# Module-Extension_V101.net
KiCad netlist of a schematic drawn in EAGLE
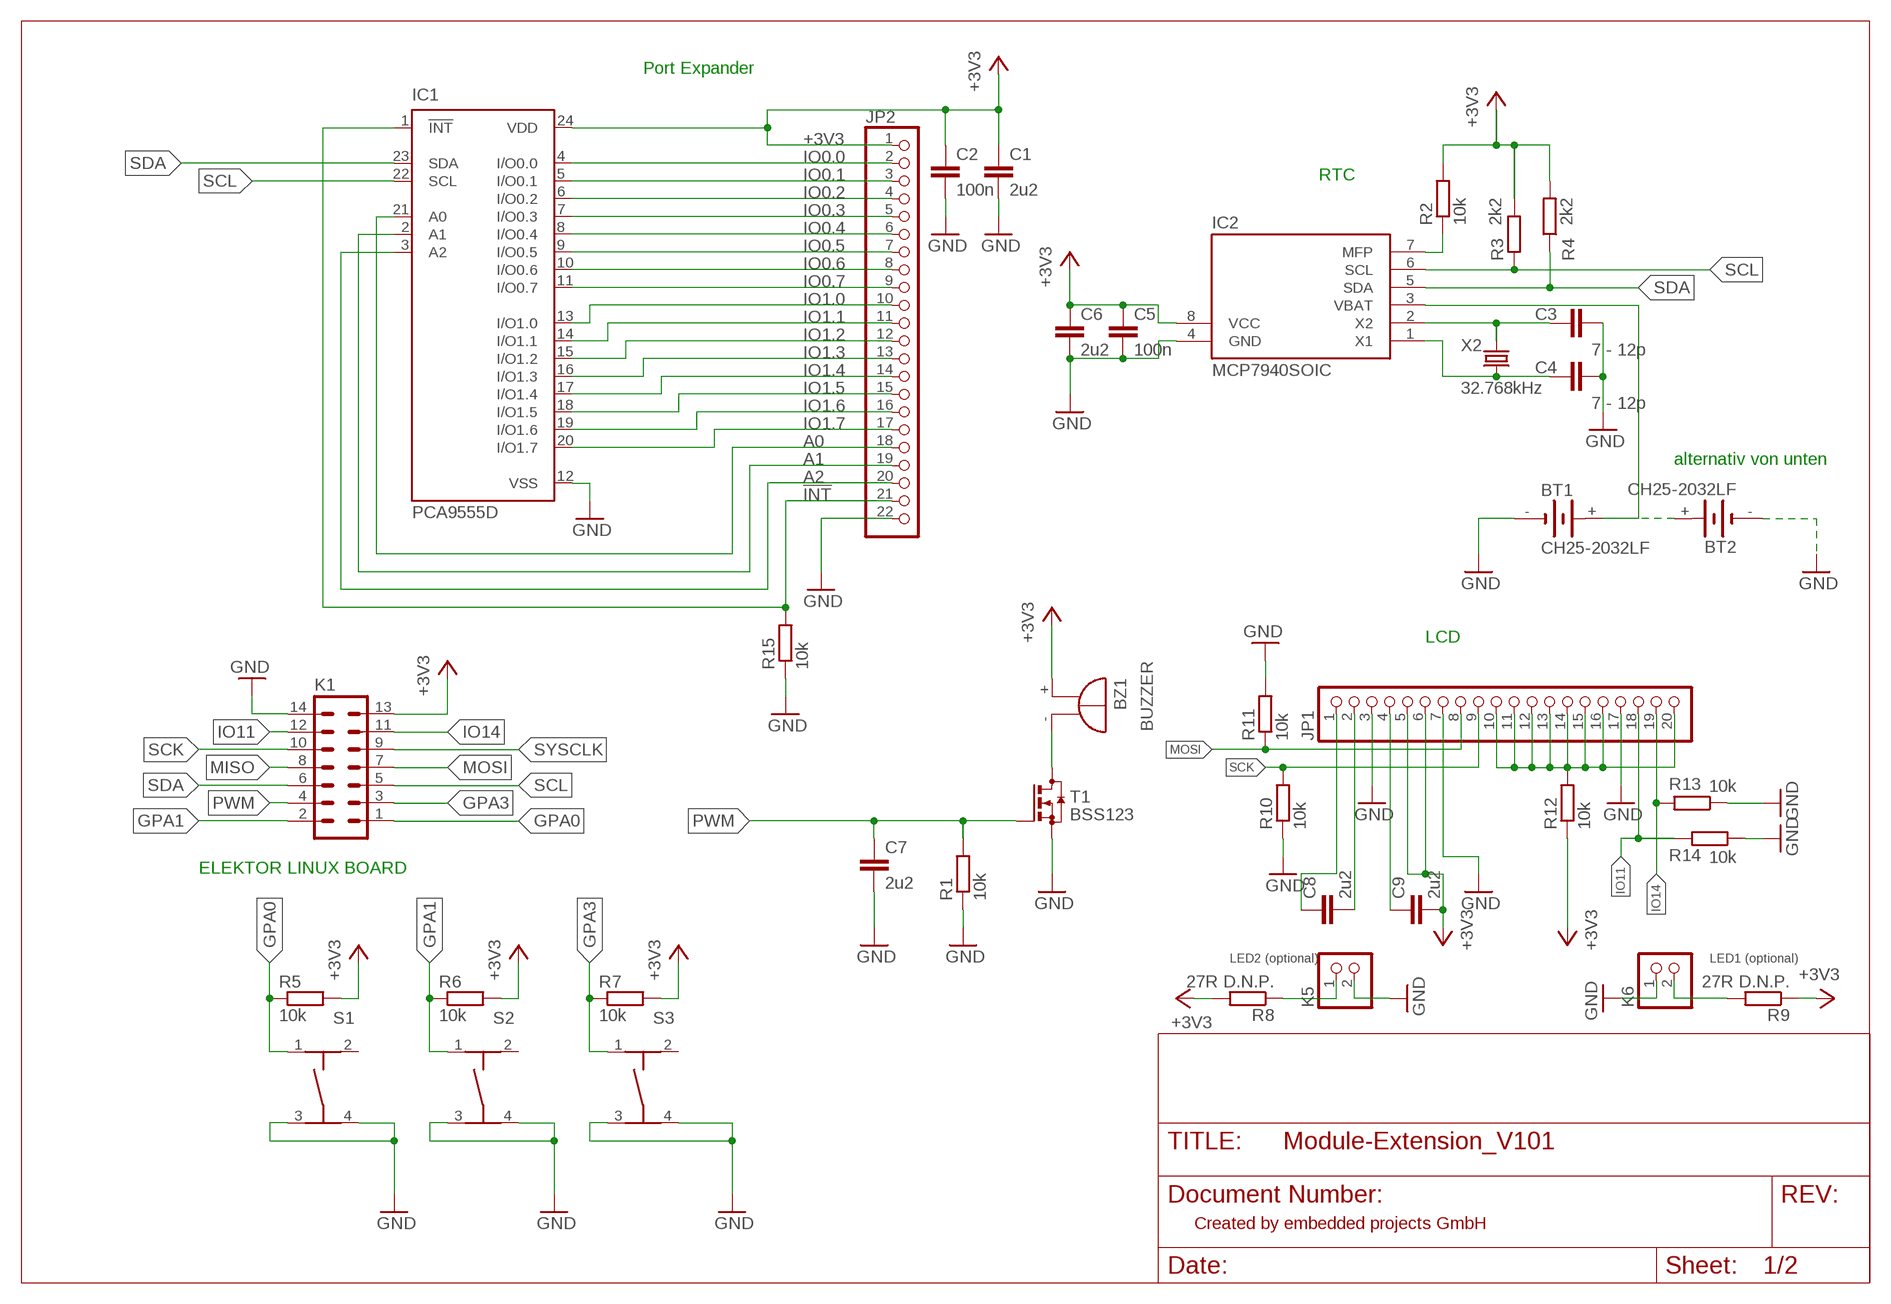
[diagram p0: schematic, sheet 1]
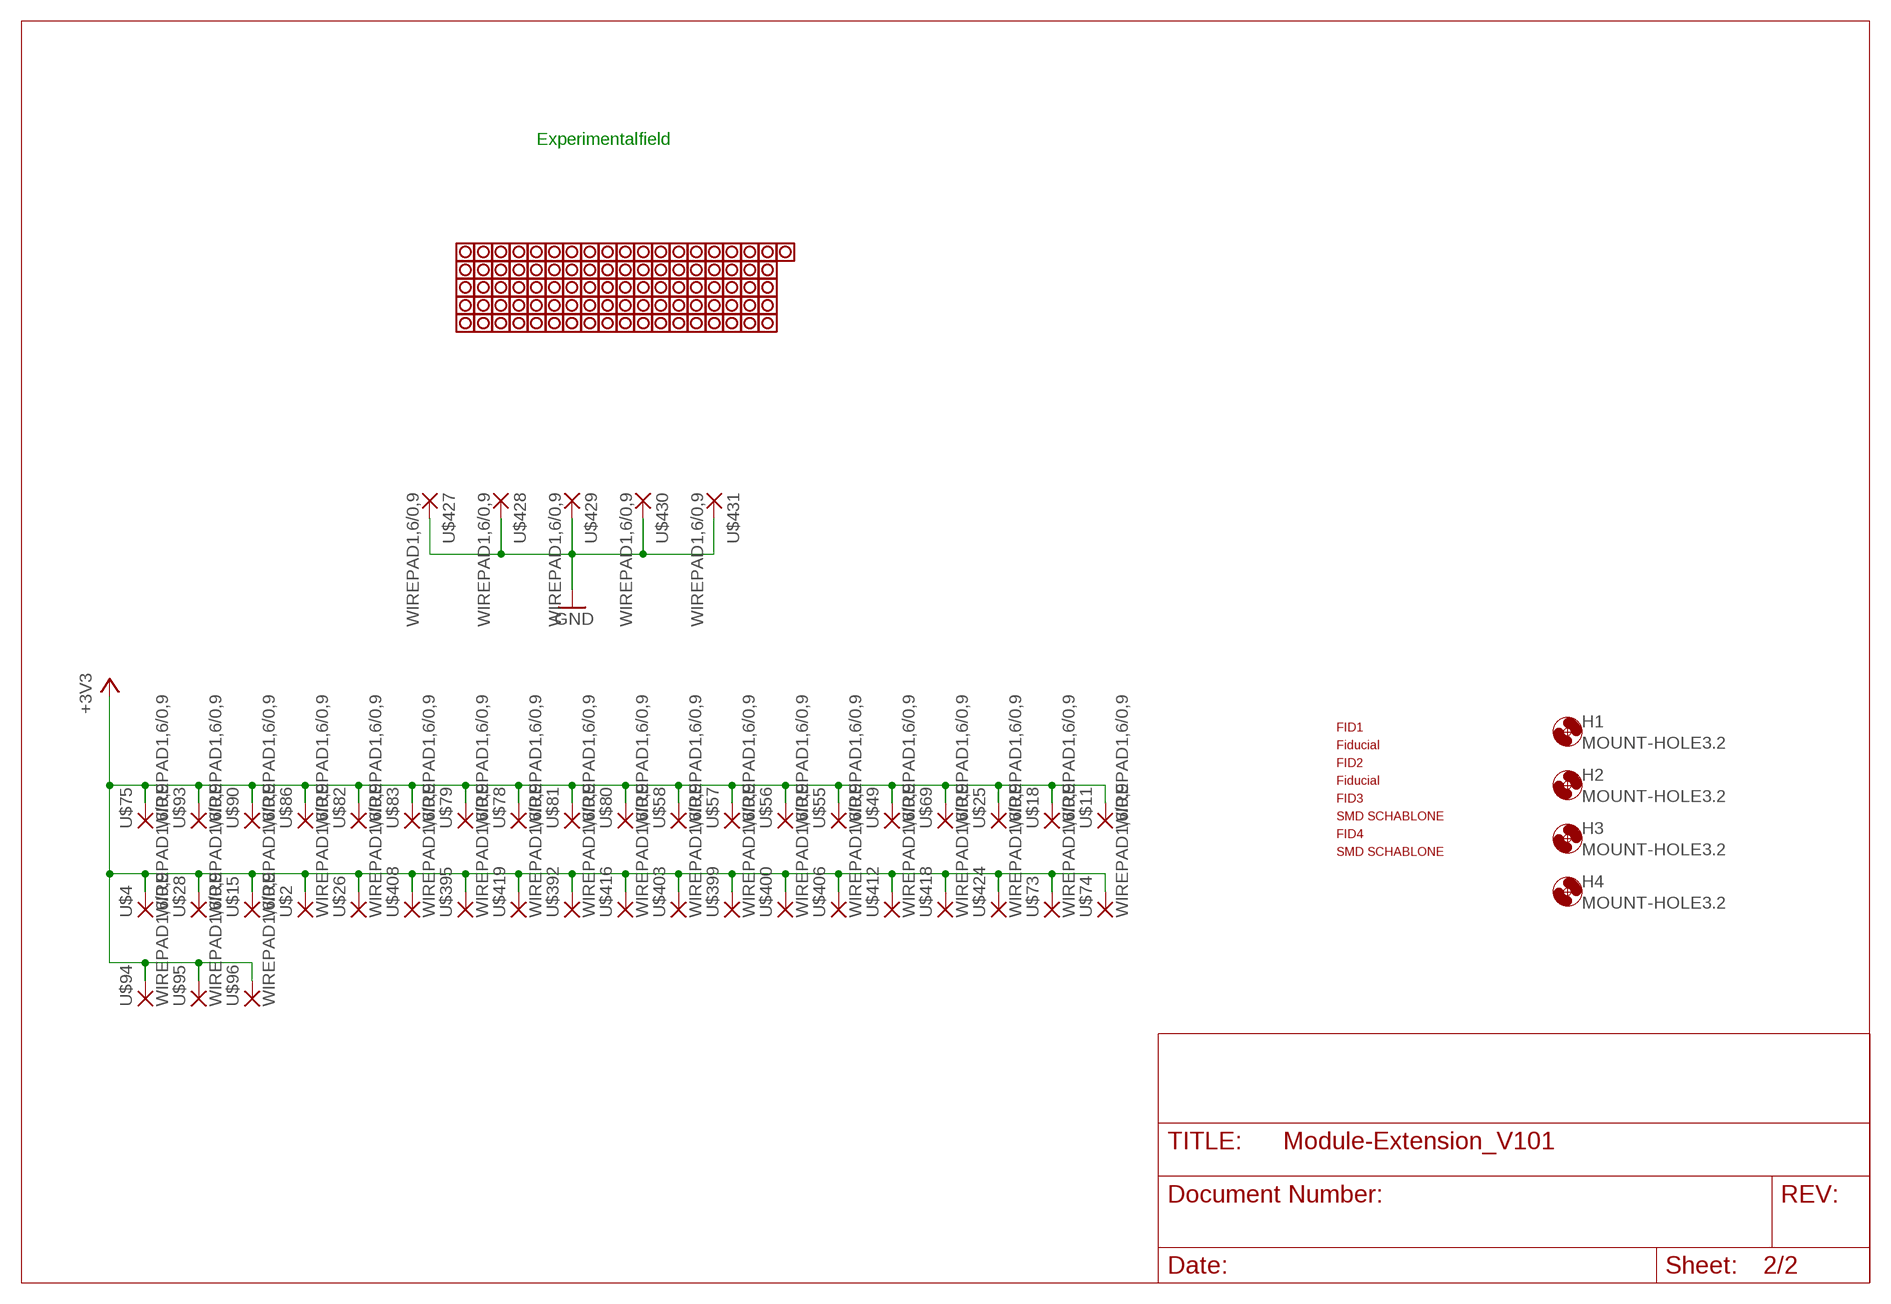
[diagram p1: schematic, sheet 2]

(export (version "E")
  (design (tool "Eeschema 10.0.6"))
  (components
    (comp (ref "BT1")
      (value "CH25-2032LF")
      (footprint "eagle-import:CH25")
      (libsource (lib "eagle-import") (part "CH25-2032LF"))
    )
    (comp (ref "BT2")
      (value "CH25-2032LF")
      (footprint "eagle-import:CH25")
      (libsource (lib "eagle-import") (part "CH25-2032LF"))
    )
    (comp (ref "BZ1")
      (value "BUZZER")
      (footprint "eagle-import:F_TMB")
      (libsource (lib "eagle-import") (part "F/TMB"))
    )
    (comp (ref "C1")
      (value "2u2")
      (footprint "eagle-import:C0805")
      (libsource (lib "eagle-import") (part "C-EUC0805"))
    )
    (comp (ref "C2")
      (value "100n")
      (footprint "eagle-import:C0805")
      (libsource (lib "eagle-import") (part "C-EUC0805"))
    )
    (comp (ref "C3")
      (value "7 - 12p")
      (footprint "eagle-import:C0805")
      (libsource (lib "eagle-import") (part "C-EUC0805"))
    )
    (comp (ref "C4")
      (value "7 - 12p")
      (footprint "eagle-import:C0805")
      (libsource (lib "eagle-import") (part "C-EUC0805"))
    )
    (comp (ref "C5")
      (value "100n")
      (footprint "eagle-import:C0805")
      (libsource (lib "eagle-import") (part "C-EUC0805"))
    )
    (comp (ref "C6")
      (value "2u2")
      (footprint "eagle-import:C0805")
      (libsource (lib "eagle-import") (part "C-EUC0805"))
    )
    (comp (ref "C7")
      (value "2u2")
      (footprint "eagle-import:C0805")
      (libsource (lib "eagle-import") (part "C-EUC0805"))
    )
    (comp (ref "C8")
      (value "2u2")
      (footprint "eagle-import:C0805")
      (libsource (lib "eagle-import") (part "C-EUC0805"))
    )
    (comp (ref "C9")
      (value "2u2")
      (footprint "eagle-import:C0805")
      (libsource (lib "eagle-import") (part "C-EUC0805"))
    )
    (comp (ref "IC1")
      (value "PCA9555D")
      (footprint "eagle-import:SO24")
      (fields (field (name "MPN") "PCA9555DW") (field (name "OC_FARNELL") "8906076"))
      (libsource (lib "eagle-import") (part "PCA9555D"))
    )
    (comp (ref "IC2")
      (value "MCP7940SOIC")
      (footprint "eagle-import:SOIC-8")
      (libsource (lib "eagle-import") (part "MCP7940SOIC"))
    )
    (comp (ref "JP1")
      (value "PINHD-1X20")
      (footprint "eagle-import:1X20")
      (libsource (lib "eagle-import") (part "PINHD-1X20"))
    )
    (comp (ref "JP2")
      (value "PINHD-1X22")
      (footprint "eagle-import:1X22")
      (libsource (lib "eagle-import") (part "PINHD-1X22"))
    )
    (comp (ref "K1")
      (value "ML14")
      (footprint "eagle-import:ML14")
      (libsource (lib "eagle-import") (part "ML14"))
    )
    (comp (ref "K5")
      (value "PINHD-1X2")
      (footprint "eagle-import:1X02")
      (libsource (lib "eagle-import") (part "PINHD-1X2"))
    )
    (comp (ref "K6")
      (value "PINHD-1X2")
      (footprint "eagle-import:1X02")
      (libsource (lib "eagle-import") (part "PINHD-1X2"))
    )
    (comp (ref "R1")
      (value "10k")
      (footprint "eagle-import:R0805")
      (libsource (lib "eagle-import") (part "R-EU_R0805"))
    )
    (comp (ref "R2")
      (value "10k")
      (footprint "eagle-import:R0805")
      (libsource (lib "eagle-import") (part "R-EU_R0805"))
    )
    (comp (ref "R3")
      (value "2k2")
      (footprint "eagle-import:R0805")
      (libsource (lib "eagle-import") (part "R-EU_R0805"))
    )
    (comp (ref "R4")
      (value "2k2")
      (footprint "eagle-import:R0805")
      (libsource (lib "eagle-import") (part "R-EU_R0805"))
    )
    (comp (ref "R5")
      (value "10k")
      (footprint "eagle-import:R0805")
      (libsource (lib "eagle-import") (part "R-EU_R0805"))
    )
    (comp (ref "R6")
      (value "10k")
      (footprint "eagle-import:R0805")
      (libsource (lib "eagle-import") (part "R-EU_R0805"))
    )
    (comp (ref "R7")
      (value "10k")
      (footprint "eagle-import:R0805")
      (libsource (lib "eagle-import") (part "R-EU_R0805"))
    )
    (comp (ref "R8")
      (value "27R D.N.P.")
      (footprint "eagle-import:R0805")
      (libsource (lib "eagle-import") (part "R-EU_R0805"))
    )
    (comp (ref "R9")
      (value "27R D.N.P.")
      (footprint "eagle-import:R0805")
      (libsource (lib "eagle-import") (part "R-EU_R0805"))
    )
    (comp (ref "R10")
      (value "10k")
      (footprint "eagle-import:R0805")
      (libsource (lib "eagle-import") (part "R-EU_R0805"))
    )
    (comp (ref "R11")
      (value "10k")
      (footprint "eagle-import:R0805")
      (libsource (lib "eagle-import") (part "R-EU_R0805"))
    )
    (comp (ref "R12")
      (value "10k")
      (footprint "eagle-import:R0805")
      (libsource (lib "eagle-import") (part "R-EU_R0805"))
    )
    (comp (ref "R13")
      (value "10k")
      (footprint "eagle-import:R0805")
      (libsource (lib "eagle-import") (part "R-EU_R0805"))
    )
    (comp (ref "R14")
      (value "10k")
      (footprint "eagle-import:R0805")
      (libsource (lib "eagle-import") (part "R-EU_R0805"))
    )
    (comp (ref "R15")
      (value "10k")
      (footprint "eagle-import:R0805")
      (libsource (lib "eagle-import") (part "R-EU_R0805"))
    )
    (comp (ref "S1")
      (value "ERGAENZUNG_TASTER-9314_SMD")
      (footprint "eagle-import:ERGAENZUNG_TASTER-9314_SMD")
      (libsource (lib "eagle-import") (part "ERGAENZUNG_TASTER-9314_SMD"))
    )
    (comp (ref "S2")
      (value "ERGAENZUNG_TASTER-9314_SMD")
      (footprint "eagle-import:ERGAENZUNG_TASTER-9314_SMD")
      (libsource (lib "eagle-import") (part "ERGAENZUNG_TASTER-9314_SMD"))
    )
    (comp (ref "S3")
      (value "ERGAENZUNG_TASTER-9314_SMD")
      (footprint "eagle-import:ERGAENZUNG_TASTER-9314_SMD")
      (libsource (lib "eagle-import") (part "ERGAENZUNG_TASTER-9314_SMD"))
    )
    (comp (ref "T1")
      (value "BSS123")
      (footprint "eagle-import:SOT23")
      (libsource (lib "eagle-import") (part "BSS123"))
    )
    (comp (ref "X2")
      (value "32.768kHz")
      (footprint "eagle-import:TC26H")
      (libsource (lib "eagle-import") (part "CRYSTALTC26H"))
    )
    (comp (ref "FID1")
      (value "PASSERMARKEN_FIDUCIAL")
      (footprint "eagle-import:PASSERMARKEN_FIDUCIAL")
      (libsource (lib "eagle-import") (part "PASSERMARKEN_FIDUCIAL"))
    )
    (comp (ref "FID2")
      (value "PASSERMARKEN_FIDUCIAL")
      (footprint "eagle-import:PASSERMARKEN_FIDUCIAL")
      (libsource (lib "eagle-import") (part "PASSERMARKEN_FIDUCIAL"))
    )
    (comp (ref "FID3")
      (value "PASSERMARKEN_FIDUCIAL")
      (footprint "eagle-import:PASSERMARKEN_FIDUCIAL")
      (libsource (lib "eagle-import") (part "SMDSCHABLONE_PASSERMARKEN_FIDUCIAL"))
    )
    (comp (ref "FID4")
      (value "PASSERMARKEN_FIDUCIAL")
      (footprint "eagle-import:PASSERMARKEN_FIDUCIAL")
      (libsource (lib "eagle-import") (part "SMDSCHABLONE_PASSERMARKEN_FIDUCIAL"))
    )
    (comp (ref "H1")
      (value "MOUNT-HOLE3.2")
      (footprint "eagle-import:3,2")
      (libsource (lib "eagle-import") (part "MOUNT-HOLE3.2"))
    )
    (comp (ref "H2")
      (value "MOUNT-HOLE3.2")
      (footprint "eagle-import:3,2")
      (libsource (lib "eagle-import") (part "MOUNT-HOLE3.2"))
    )
    (comp (ref "H3")
      (value "MOUNT-HOLE3.2")
      (footprint "eagle-import:3,2")
      (libsource (lib "eagle-import") (part "MOUNT-HOLE3.2"))
    )
    (comp (ref "H4")
      (value "MOUNT-HOLE3.2")
      (footprint "eagle-import:3,2")
      (libsource (lib "eagle-import") (part "MOUNT-HOLE3.2"))
    )
    (comp (ref "U$2")
      (value "WIREPAD1,6/0,9")
      (footprint "eagle-import:1,6_0,9")
      (libsource (lib "eagle-import") (part "WIREPAD1,6/0,9"))
    )
    (comp (ref "U$3")
      (value "VIAS")
      (footprint "eagle-import:VIAS")
      (libsource (lib "eagle-import") (part "VIAS"))
    )
    (comp (ref "U$4")
      (value "WIREPAD1,6/0,9")
      (footprint "eagle-import:1,6_0,9")
      (libsource (lib "eagle-import") (part "WIREPAD1,6/0,9"))
    )
    (comp (ref "U$5")
      (value "VIAS")
      (footprint "eagle-import:VIAS")
      (libsource (lib "eagle-import") (part "VIAS"))
    )
    (comp (ref "U$6")
      (value "VIAS")
      (footprint "eagle-import:VIAS")
      (libsource (lib "eagle-import") (part "VIAS"))
    )
    (comp (ref "U$7")
      (value "VIAS")
      (footprint "eagle-import:VIAS")
      (libsource (lib "eagle-import") (part "VIAS"))
    )
    (comp (ref "U$8")
      (value "VIAS")
      (footprint "eagle-import:VIAS")
      (libsource (lib "eagle-import") (part "VIAS"))
    )
    (comp (ref "U$9")
      (value "VIAS")
      (footprint "eagle-import:VIAS")
      (libsource (lib "eagle-import") (part "VIAS"))
    )
    (comp (ref "U$10")
      (value "VIAS")
      (footprint "eagle-import:VIAS")
      (libsource (lib "eagle-import") (part "VIAS"))
    )
    (comp (ref "U$11")
      (value "WIREPAD1,6/0,9")
      (footprint "eagle-import:1,6_0,9")
      (libsource (lib "eagle-import") (part "WIREPAD1,6/0,9"))
    )
    (comp (ref "U$12")
      (value "VIAS")
      (footprint "eagle-import:VIAS")
      (libsource (lib "eagle-import") (part "VIAS"))
    )
    (comp (ref "U$13")
      (value "VIAS")
      (footprint "eagle-import:VIAS")
      (libsource (lib "eagle-import") (part "VIAS"))
    )
    (comp (ref "U$14")
      (value "VIAS")
      (footprint "eagle-import:VIAS")
      (libsource (lib "eagle-import") (part "VIAS"))
    )
    (comp (ref "U$15")
      (value "WIREPAD1,6/0,9")
      (footprint "eagle-import:1,6_0,9")
      (libsource (lib "eagle-import") (part "WIREPAD1,6/0,9"))
    )
    (comp (ref "U$16")
      (value "VIAS")
      (footprint "eagle-import:VIAS")
      (libsource (lib "eagle-import") (part "VIAS"))
    )
    (comp (ref "U$17")
      (value "VIAS")
      (footprint "eagle-import:VIAS")
      (libsource (lib "eagle-import") (part "VIAS"))
    )
    (comp (ref "U$18")
      (value "WIREPAD1,6/0,9")
      (footprint "eagle-import:1,6_0,9")
      (libsource (lib "eagle-import") (part "WIREPAD1,6/0,9"))
    )
    (comp (ref "U$19")
      (value "VIAS")
      (footprint "eagle-import:VIAS")
      (libsource (lib "eagle-import") (part "VIAS"))
    )
    (comp (ref "U$20")
      (value "VIAS")
      (footprint "eagle-import:VIAS")
      (libsource (lib "eagle-import") (part "VIAS"))
    )
    (comp (ref "U$21")
      (value "VIAS")
      (footprint "eagle-import:VIAS")
      (libsource (lib "eagle-import") (part "VIAS"))
    )
    (comp (ref "U$22")
      (value "VIAS")
      (footprint "eagle-import:VIAS")
      (libsource (lib "eagle-import") (part "VIAS"))
    )
    (comp (ref "U$23")
      (value "VIAS")
      (footprint "eagle-import:VIAS")
      (libsource (lib "eagle-import") (part "VIAS"))
    )
    (comp (ref "U$24")
      (value "VIAS")
      (footprint "eagle-import:VIAS")
      (libsource (lib "eagle-import") (part "VIAS"))
    )
    (comp (ref "U$25")
      (value "WIREPAD1,6/0,9")
      (footprint "eagle-import:1,6_0,9")
      (libsource (lib "eagle-import") (part "WIREPAD1,6/0,9"))
    )
    (comp (ref "U$26")
      (value "WIREPAD1,6/0,9")
      (footprint "eagle-import:1,6_0,9")
      (libsource (lib "eagle-import") (part "WIREPAD1,6/0,9"))
    )
    (comp (ref "U$27")
      (value "VIAS")
      (footprint "eagle-import:VIAS")
      (libsource (lib "eagle-import") (part "VIAS"))
    )
    (comp (ref "U$28")
      (value "WIREPAD1,6/0,9")
      (footprint "eagle-import:1,6_0,9")
      (libsource (lib "eagle-import") (part "WIREPAD1,6/0,9"))
    )
    (comp (ref "U$29")
      (value "VIAS")
      (footprint "eagle-import:VIAS")
      (libsource (lib "eagle-import") (part "VIAS"))
    )
    (comp (ref "U$30")
      (value "VIAS")
      (footprint "eagle-import:VIAS")
      (libsource (lib "eagle-import") (part "VIAS"))
    )
    (comp (ref "U$31")
      (value "VIAS")
      (footprint "eagle-import:VIAS")
      (libsource (lib "eagle-import") (part "VIAS"))
    )
    (comp (ref "U$32")
      (value "VIAS")
      (footprint "eagle-import:VIAS")
      (libsource (lib "eagle-import") (part "VIAS"))
    )
    (comp (ref "U$33")
      (value "VIAS")
      (footprint "eagle-import:VIAS")
      (libsource (lib "eagle-import") (part "VIAS"))
    )
    (comp (ref "U$34")
      (value "VIAS")
      (footprint "eagle-import:VIAS")
      (libsource (lib "eagle-import") (part "VIAS"))
    )
    (comp (ref "U$35")
      (value "VIAS")
      (footprint "eagle-import:VIAS")
      (libsource (lib "eagle-import") (part "VIAS"))
    )
    (comp (ref "U$36")
      (value "VIAS")
      (footprint "eagle-import:VIAS")
      (libsource (lib "eagle-import") (part "VIAS"))
    )
    (comp (ref "U$37")
      (value "VIAS")
      (footprint "eagle-import:VIAS")
      (libsource (lib "eagle-import") (part "VIAS"))
    )
    (comp (ref "U$38")
      (value "VIAS")
      (footprint "eagle-import:VIAS")
      (libsource (lib "eagle-import") (part "VIAS"))
    )
    (comp (ref "U$39")
      (value "VIAS")
      (footprint "eagle-import:VIAS")
      (libsource (lib "eagle-import") (part "VIAS"))
    )
    (comp (ref "U$40")
      (value "VIAS")
      (footprint "eagle-import:VIAS")
      (libsource (lib "eagle-import") (part "VIAS"))
    )
    (comp (ref "U$41")
      (value "VIAS")
      (footprint "eagle-import:VIAS")
      (libsource (lib "eagle-import") (part "VIAS"))
    )
    (comp (ref "U$42")
      (value "VIAS")
      (footprint "eagle-import:VIAS")
      (libsource (lib "eagle-import") (part "VIAS"))
    )
    (comp (ref "U$43")
      (value "VIAS")
      (footprint "eagle-import:VIAS")
      (libsource (lib "eagle-import") (part "VIAS"))
    )
    (comp (ref "U$44")
      (value "VIAS")
      (footprint "eagle-import:VIAS")
      (libsource (lib "eagle-import") (part "VIAS"))
    )
    (comp (ref "U$45")
      (value "VIAS")
      (footprint "eagle-import:VIAS")
      (libsource (lib "eagle-import") (part "VIAS"))
    )
    (comp (ref "U$46")
      (value "VIAS")
      (footprint "eagle-import:VIAS")
      (libsource (lib "eagle-import") (part "VIAS"))
    )
    (comp (ref "U$47")
      (value "VIAS")
      (footprint "eagle-import:VIAS")
      (libsource (lib "eagle-import") (part "VIAS"))
    )
    (comp (ref "U$48")
      (value "VIAS")
      (footprint "eagle-import:VIAS")
      (libsource (lib "eagle-import") (part "VIAS"))
    )
    (comp (ref "U$49")
      (value "WIREPAD1,6/0,9")
      (footprint "eagle-import:1,6_0,9")
      (libsource (lib "eagle-import") (part "WIREPAD1,6/0,9"))
    )
    (comp (ref "U$50")
      (value "VIAS")
      (footprint "eagle-import:VIAS")
      (libsource (lib "eagle-import") (part "VIAS"))
    )
    (comp (ref "U$51")
      (value "VIAS")
      (footprint "eagle-import:VIAS")
      (libsource (lib "eagle-import") (part "VIAS"))
    )
    (comp (ref "U$52")
      (value "VIAS")
      (footprint "eagle-import:VIAS")
      (libsource (lib "eagle-import") (part "VIAS"))
    )
    (comp (ref "U$53")
      (value "VIAS")
      (footprint "eagle-import:VIAS")
      (libsource (lib "eagle-import") (part "VIAS"))
    )
    (comp (ref "U$54")
      (value "VIAS")
      (footprint "eagle-import:VIAS")
      (libsource (lib "eagle-import") (part "VIAS"))
    )
    (comp (ref "U$55")
      (value "WIREPAD1,6/0,9")
      (footprint "eagle-import:1,6_0,9")
      (libsource (lib "eagle-import") (part "WIREPAD1,6/0,9"))
    )
    (comp (ref "U$56")
      (value "WIREPAD1,6/0,9")
      (footprint "eagle-import:1,6_0,9")
      (libsource (lib "eagle-import") (part "WIREPAD1,6/0,9"))
    )
    (comp (ref "U$57")
      (value "WIREPAD1,6/0,9")
      (footprint "eagle-import:1,6_0,9")
      (libsource (lib "eagle-import") (part "WIREPAD1,6/0,9"))
    )
    (comp (ref "U$58")
      (value "WIREPAD1,6/0,9")
      (footprint "eagle-import:1,6_0,9")
      (libsource (lib "eagle-import") (part "WIREPAD1,6/0,9"))
    )
    (comp (ref "U$59")
      (value "VIAS")
      (footprint "eagle-import:VIAS")
      (libsource (lib "eagle-import") (part "VIAS"))
    )
    (comp (ref "U$60")
      (value "VIAS")
      (footprint "eagle-import:VIAS")
      (libsource (lib "eagle-import") (part "VIAS"))
    )
    (comp (ref "U$61")
      (value "VIAS")
      (footprint "eagle-import:VIAS")
      (libsource (lib "eagle-import") (part "VIAS"))
    )
    (comp (ref "U$62")
      (value "VIAS")
      (footprint "eagle-import:VIAS")
      (libsource (lib "eagle-import") (part "VIAS"))
    )
    (comp (ref "U$63")
      (value "VIAS")
      (footprint "eagle-import:VIAS")
      (libsource (lib "eagle-import") (part "VIAS"))
    )
    (comp (ref "U$64")
      (value "VIAS")
      (footprint "eagle-import:VIAS")
      (libsource (lib "eagle-import") (part "VIAS"))
    )
    (comp (ref "U$65")
      (value "VIAS")
      (footprint "eagle-import:VIAS")
      (libsource (lib "eagle-import") (part "VIAS"))
    )
    (comp (ref "U$66")
      (value "VIAS")
      (footprint "eagle-import:VIAS")
      (libsource (lib "eagle-import") (part "VIAS"))
    )
    (comp (ref "U$67")
      (value "VIAS")
      (footprint "eagle-import:VIAS")
      (libsource (lib "eagle-import") (part "VIAS"))
    )
    (comp (ref "U$68")
      (value "VIAS")
      (footprint "eagle-import:VIAS")
      (libsource (lib "eagle-import") (part "VIAS"))
    )
    (comp (ref "U$69")
      (value "WIREPAD1,6/0,9")
      (footprint "eagle-import:1,6_0,9")
      (libsource (lib "eagle-import") (part "WIREPAD1,6/0,9"))
    )
    (comp (ref "U$70")
      (value "VIAS")
      (footprint "eagle-import:VIAS")
      (libsource (lib "eagle-import") (part "VIAS"))
    )
    (comp (ref "U$71")
      (value "VIAS")
      (footprint "eagle-import:VIAS")
      (libsource (lib "eagle-import") (part "VIAS"))
    )
    (comp (ref "U$72")
      (value "VIAS")
      (footprint "eagle-import:VIAS")
      (libsource (lib "eagle-import") (part "VIAS"))
    )
    (comp (ref "U$73")
      (value "WIREPAD1,6/0,9")
      (footprint "eagle-import:1,6_0,9")
      (libsource (lib "eagle-import") (part "WIREPAD1,6/0,9"))
    )
    (comp (ref "U$74")
      (value "WIREPAD1,6/0,9")
      (footprint "eagle-import:1,6_0,9")
      (libsource (lib "eagle-import") (part "WIREPAD1,6/0,9"))
    )
    (comp (ref "U$75")
      (value "WIREPAD1,6/0,9")
      (footprint "eagle-import:1,6_0,9")
      (libsource (lib "eagle-import") (part "WIREPAD1,6/0,9"))
    )
    (comp (ref "U$76")
      (value "VIAS")
      (footprint "eagle-import:VIAS")
      (libsource (lib "eagle-import") (part "VIAS"))
    )
    (comp (ref "U$77")
      (value "VIAS")
      (footprint "eagle-import:VIAS")
      (libsource (lib "eagle-import") (part "VIAS"))
    )
    (comp (ref "U$78")
      (value "WIREPAD1,6/0,9")
      (footprint "eagle-import:1,6_0,9")
      (libsource (lib "eagle-import") (part "WIREPAD1,6/0,9"))
    )
    (comp (ref "U$79")
      (value "WIREPAD1,6/0,9")
      (footprint "eagle-import:1,6_0,9")
      (libsource (lib "eagle-import") (part "WIREPAD1,6/0,9"))
    )
    (comp (ref "U$80")
      (value "WIREPAD1,6/0,9")
      (footprint "eagle-import:1,6_0,9")
      (libsource (lib "eagle-import") (part "WIREPAD1,6/0,9"))
    )
    (comp (ref "U$81")
      (value "WIREPAD1,6/0,9")
      (footprint "eagle-import:1,6_0,9")
      (libsource (lib "eagle-import") (part "WIREPAD1,6/0,9"))
    )
    (comp (ref "U$82")
      (value "WIREPAD1,6/0,9")
      (footprint "eagle-import:1,6_0,9")
      (libsource (lib "eagle-import") (part "WIREPAD1,6/0,9"))
    )
    (comp (ref "U$83")
      (value "WIREPAD1,6/0,9")
      (footprint "eagle-import:1,6_0,9")
      (libsource (lib "eagle-import") (part "WIREPAD1,6/0,9"))
    )
    (comp (ref "U$84")
      (value "VIAS")
      (footprint "eagle-import:VIAS")
      (libsource (lib "eagle-import") (part "VIAS"))
    )
    (comp (ref "U$85")
      (value "VIAS")
      (footprint "eagle-import:VIAS")
      (libsource (lib "eagle-import") (part "VIAS"))
    )
    (comp (ref "U$86")
      (value "WIREPAD1,6/0,9")
      (footprint "eagle-import:1,6_0,9")
      (libsource (lib "eagle-import") (part "WIREPAD1,6/0,9"))
    )
    (comp (ref "U$87")
      (value "VIAS")
      (footprint "eagle-import:VIAS")
      (libsource (lib "eagle-import") (part "VIAS"))
    )
    (comp (ref "U$88")
      (value "VIAS")
      (footprint "eagle-import:VIAS")
      (libsource (lib "eagle-import") (part "VIAS"))
    )
    (comp (ref "U$89")
      (value "VIAS")
      (footprint "eagle-import:VIAS")
      (libsource (lib "eagle-import") (part "VIAS"))
    )
    (comp (ref "U$90")
      (value "WIREPAD1,6/0,9")
      (footprint "eagle-import:1,6_0,9")
      (libsource (lib "eagle-import") (part "WIREPAD1,6/0,9"))
    )
    (comp (ref "U$91")
      (value "VIAS")
      (footprint "eagle-import:VIAS")
      (libsource (lib "eagle-import") (part "VIAS"))
    )
    (comp (ref "U$92")
      (value "VIAS")
      (footprint "eagle-import:VIAS")
      (libsource (lib "eagle-import") (part "VIAS"))
    )
    (comp (ref "U$93")
      (value "WIREPAD1,6/0,9")
      (footprint "eagle-import:1,6_0,9")
      (libsource (lib "eagle-import") (part "WIREPAD1,6/0,9"))
    )
    (comp (ref "U$94")
      (value "WIREPAD1,6/0,9")
      (footprint "eagle-import:1,6_0,9")
      (libsource (lib "eagle-import") (part "WIREPAD1,6/0,9"))
    )
    (comp (ref "U$95")
      (value "WIREPAD1,6/0,9")
      (footprint "eagle-import:1,6_0,9")
      (libsource (lib "eagle-import") (part "WIREPAD1,6/0,9"))
    )
    (comp (ref "U$96")
      (value "WIREPAD1,6/0,9")
      (footprint "eagle-import:1,6_0,9")
      (libsource (lib "eagle-import") (part "WIREPAD1,6/0,9"))
    )
    (comp (ref "U$391")
      (value "VIAS")
      (footprint "eagle-import:VIAS")
      (libsource (lib "eagle-import") (part "VIAS"))
    )
    (comp (ref "U$392")
      (value "WIREPAD1,6/0,9")
      (footprint "eagle-import:1,6_0,9")
      (libsource (lib "eagle-import") (part "WIREPAD1,6/0,9"))
    )
    (comp (ref "U$393")
      (value "VIAS")
      (footprint "eagle-import:VIAS")
      (libsource (lib "eagle-import") (part "VIAS"))
    )
    (comp (ref "U$394")
      (value "VIAS")
      (footprint "eagle-import:VIAS")
      (libsource (lib "eagle-import") (part "VIAS"))
    )
    (comp (ref "U$395")
      (value "WIREPAD1,6/0,9")
      (footprint "eagle-import:1,6_0,9")
      (libsource (lib "eagle-import") (part "WIREPAD1,6/0,9"))
    )
    (comp (ref "U$396")
      (value "VIAS")
      (footprint "eagle-import:VIAS")
      (libsource (lib "eagle-import") (part "VIAS"))
    )
    (comp (ref "U$397")
      (value "VIAS")
      (footprint "eagle-import:VIAS")
      (libsource (lib "eagle-import") (part "VIAS"))
    )
    (comp (ref "U$398")
      (value "VIAS")
      (footprint "eagle-import:VIAS")
      (libsource (lib "eagle-import") (part "VIAS"))
    )
    (comp (ref "U$399")
      (value "WIREPAD1,6/0,9")
      (footprint "eagle-import:1,6_0,9")
      (libsource (lib "eagle-import") (part "WIREPAD1,6/0,9"))
    )
    (comp (ref "U$400")
      (value "WIREPAD1,6/0,9")
      (footprint "eagle-import:1,6_0,9")
      (libsource (lib "eagle-import") (part "WIREPAD1,6/0,9"))
    )
    (comp (ref "U$401")
      (value "VIAS")
      (footprint "eagle-import:VIAS")
      (libsource (lib "eagle-import") (part "VIAS"))
    )
    (comp (ref "U$402")
      (value "VIAS")
      (footprint "eagle-import:VIAS")
      (libsource (lib "eagle-import") (part "VIAS"))
    )
    (comp (ref "U$403")
      (value "WIREPAD1,6/0,9")
      (footprint "eagle-import:1,6_0,9")
      (libsource (lib "eagle-import") (part "WIREPAD1,6/0,9"))
    )
    (comp (ref "U$404")
      (value "VIAS")
      (footprint "eagle-import:VIAS")
      (libsource (lib "eagle-import") (part "VIAS"))
    )
    (comp (ref "U$405")
      (value "VIAS")
      (footprint "eagle-import:VIAS")
      (libsource (lib "eagle-import") (part "VIAS"))
    )
    (comp (ref "U$406")
      (value "WIREPAD1,6/0,9")
      (footprint "eagle-import:1,6_0,9")
      (libsource (lib "eagle-import") (part "WIREPAD1,6/0,9"))
    )
    (comp (ref "U$407")
      (value "VIAS")
      (footprint "eagle-import:VIAS")
      (libsource (lib "eagle-import") (part "VIAS"))
    )
    (comp (ref "U$408")
      (value "WIREPAD1,6/0,9")
      (footprint "eagle-import:1,6_0,9")
      (libsource (lib "eagle-import") (part "WIREPAD1,6/0,9"))
    )
    (comp (ref "U$409")
      (value "VIAS")
      (footprint "eagle-import:VIAS")
      (libsource (lib "eagle-import") (part "VIAS"))
    )
    (comp (ref "U$410")
      (value "VIAS")
      (footprint "eagle-import:VIAS")
      (libsource (lib "eagle-import") (part "VIAS"))
    )
    (comp (ref "U$411")
      (value "VIAS")
      (footprint "eagle-import:VIAS")
      (libsource (lib "eagle-import") (part "VIAS"))
    )
    (comp (ref "U$412")
      (value "WIREPAD1,6/0,9")
      (footprint "eagle-import:1,6_0,9")
      (libsource (lib "eagle-import") (part "WIREPAD1,6/0,9"))
    )
    (comp (ref "U$413")
      (value "VIAS")
      (footprint "eagle-import:VIAS")
      (libsource (lib "eagle-import") (part "VIAS"))
    )
    (comp (ref "U$414")
      (value "VIAS")
      (footprint "eagle-import:VIAS")
      (libsource (lib "eagle-import") (part "VIAS"))
    )
    (comp (ref "U$415")
      (value "VIAS")
      (footprint "eagle-import:VIAS")
      (libsource (lib "eagle-import") (part "VIAS"))
    )
    (comp (ref "U$416")
      (value "WIREPAD1,6/0,9")
      (footprint "eagle-import:1,6_0,9")
      (libsource (lib "eagle-import") (part "WIREPAD1,6/0,9"))
    )
    (comp (ref "U$417")
      (value "VIAS")
      (footprint "eagle-import:VIAS")
      (libsource (lib "eagle-import") (part "VIAS"))
    )
    (comp (ref "U$418")
      (value "WIREPAD1,6/0,9")
      (footprint "eagle-import:1,6_0,9")
      (libsource (lib "eagle-import") (part "WIREPAD1,6/0,9"))
    )
    (comp (ref "U$419")
      (value "WIREPAD1,6/0,9")
      (footprint "eagle-import:1,6_0,9")
      (libsource (lib "eagle-import") (part "WIREPAD1,6/0,9"))
    )
    (comp (ref "U$420")
      (value "VIAS")
      (footprint "eagle-import:VIAS")
      (libsource (lib "eagle-import") (part "VIAS"))
    )
    (comp (ref "U$421")
      (value "VIAS")
      (footprint "eagle-import:VIAS")
      (libsource (lib "eagle-import") (part "VIAS"))
    )
    (comp (ref "U$422")
      (value "VIAS")
      (footprint "eagle-import:VIAS")
      (libsource (lib "eagle-import") (part "VIAS"))
    )
    (comp (ref "U$423")
      (value "VIAS")
      (footprint "eagle-import:VIAS")
      (libsource (lib "eagle-import") (part "VIAS"))
    )
    (comp (ref "U$424")
      (value "WIREPAD1,6/0,9")
      (footprint "eagle-import:1,6_0,9")
      (libsource (lib "eagle-import") (part "WIREPAD1,6/0,9"))
    )
    (comp (ref "U$425")
      (value "VIAS")
      (footprint "eagle-import:VIAS")
      (libsource (lib "eagle-import") (part "VIAS"))
    )
    (comp (ref "U$426")
      (value "VIAS")
      (footprint "eagle-import:VIAS")
      (libsource (lib "eagle-import") (part "VIAS"))
    )
    (comp (ref "U$427")
      (value "WIREPAD1,6/0,9")
      (footprint "eagle-import:1,6_0,9")
      (libsource (lib "eagle-import") (part "WIREPAD1,6/0,9"))
    )
    (comp (ref "U$428")
      (value "WIREPAD1,6/0,9")
      (footprint "eagle-import:1,6_0,9")
      (libsource (lib "eagle-import") (part "WIREPAD1,6/0,9"))
    )
    (comp (ref "U$429")
      (value "WIREPAD1,6/0,9")
      (footprint "eagle-import:1,6_0,9")
      (libsource (lib "eagle-import") (part "WIREPAD1,6/0,9"))
    )
    (comp (ref "U$430")
      (value "WIREPAD1,6/0,9")
      (footprint "eagle-import:1,6_0,9")
      (libsource (lib "eagle-import") (part "WIREPAD1,6/0,9"))
    )
    (comp (ref "U$431")
      (value "WIREPAD1,6/0,9")
      (footprint "eagle-import:1,6_0,9")
      (libsource (lib "eagle-import") (part "WIREPAD1,6/0,9"))
    )
    (comp (ref "U$432")
      (value "VIAS")
      (footprint "eagle-import:VIAS")
      (libsource (lib "eagle-import") (part "VIAS"))
    )
  )
  (nets
    (net (code "1") (name "+3V3") (class "Default")
      (node (ref "BZ1") (pin "+") (pinfunction "+_+") (pintype "passive"))
      (node (ref "C1") (pin "1") (pinfunction "1_1") (pintype "passive"))
      (node (ref "C2") (pin "1") (pinfunction "1_1") (pintype "passive"))
      (node (ref "C5") (pin "1") (pinfunction "1_1") (pintype "passive"))
      (node (ref "C6") (pin "1") (pinfunction "1_1") (pintype "passive"))
      (node (ref "C9") (pin "2") (pinfunction "2_2") (pintype "passive"))
      (node (ref "IC1") (pin "24") (pinfunction "VDD_24") (pintype "power_in"))
      (node (ref "IC2") (pin "8") (pinfunction "VCC_8") (pintype "power_in"))
      (node (ref "JP1") (pin "5") (pinfunction "5_5") (pintype "passive"))
      (node (ref "JP1") (pin "6") (pinfunction "6_6") (pintype "passive"))
      (node (ref "JP2") (pin "1") (pinfunction "1_1") (pintype "passive"))
      (node (ref "K1") (pin "13") (pinfunction "13_13") (pintype "passive"))
      (node (ref "R12") (pin "1") (pinfunction "1_1") (pintype "passive"))
      (node (ref "R2") (pin "2") (pinfunction "2_2") (pintype "passive"))
      (node (ref "R3") (pin "2") (pinfunction "2_2") (pintype "passive"))
      (node (ref "R4") (pin "2") (pinfunction "2_2") (pintype "passive"))
      (node (ref "R5") (pin "2") (pinfunction "2_2") (pintype "passive"))
      (node (ref "R6") (pin "2") (pinfunction "2_2") (pintype "passive"))
      (node (ref "R7") (pin "2") (pinfunction "2_2") (pintype "passive"))
      (node (ref "R8") (pin "2") (pinfunction "2_2") (pintype "passive"))
      (node (ref "R9") (pin "1") (pinfunction "1_1") (pintype "passive"))
      (node (ref "U$11") (pin "1") (pinfunction "P_1") (pintype "passive"))
      (node (ref "U$15") (pin "1") (pinfunction "P_1") (pintype "passive"))
      (node (ref "U$18") (pin "1") (pinfunction "P_1") (pintype "passive"))
      (node (ref "U$2") (pin "1") (pinfunction "P_1") (pintype "passive"))
      (node (ref "U$25") (pin "1") (pinfunction "P_1") (pintype "passive"))
      (node (ref "U$26") (pin "1") (pinfunction "P_1") (pintype "passive"))
      (node (ref "U$28") (pin "1") (pinfunction "P_1") (pintype "passive"))
      (node (ref "U$392") (pin "1") (pinfunction "P_1") (pintype "passive"))
      (node (ref "U$395") (pin "1") (pinfunction "P_1") (pintype "passive"))
      (node (ref "U$399") (pin "1") (pinfunction "P_1") (pintype "passive"))
      (node (ref "U$4") (pin "1") (pinfunction "P_1") (pintype "passive"))
      (node (ref "U$400") (pin "1") (pinfunction "P_1") (pintype "passive"))
      (node (ref "U$403") (pin "1") (pinfunction "P_1") (pintype "passive"))
      (node (ref "U$406") (pin "1") (pinfunction "P_1") (pintype "passive"))
      (node (ref "U$408") (pin "1") (pinfunction "P_1") (pintype "passive"))
      (node (ref "U$412") (pin "1") (pinfunction "P_1") (pintype "passive"))
      (node (ref "U$416") (pin "1") (pinfunction "P_1") (pintype "passive"))
      (node (ref "U$418") (pin "1") (pinfunction "P_1") (pintype "passive"))
      (node (ref "U$419") (pin "1") (pinfunction "P_1") (pintype "passive"))
      (node (ref "U$424") (pin "1") (pinfunction "P_1") (pintype "passive"))
      (node (ref "U$49") (pin "1") (pinfunction "P_1") (pintype "passive"))
      (node (ref "U$55") (pin "1") (pinfunction "P_1") (pintype "passive"))
      (node (ref "U$56") (pin "1") (pinfunction "P_1") (pintype "passive"))
      (node (ref "U$57") (pin "1") (pinfunction "P_1") (pintype "passive"))
      (node (ref "U$58") (pin "1") (pinfunction "P_1") (pintype "passive"))
      (node (ref "U$69") (pin "1") (pinfunction "P_1") (pintype "passive"))
      (node (ref "U$73") (pin "1") (pinfunction "P_1") (pintype "passive"))
      (node (ref "U$74") (pin "1") (pinfunction "P_1") (pintype "passive"))
      (node (ref "U$75") (pin "1") (pinfunction "P_1") (pintype "passive"))
      (node (ref "U$78") (pin "1") (pinfunction "P_1") (pintype "passive"))
      (node (ref "U$79") (pin "1") (pinfunction "P_1") (pintype "passive"))
      (node (ref "U$80") (pin "1") (pinfunction "P_1") (pintype "passive"))
      (node (ref "U$81") (pin "1") (pinfunction "P_1") (pintype "passive"))
      (node (ref "U$82") (pin "1") (pinfunction "P_1") (pintype "passive"))
      (node (ref "U$83") (pin "1") (pinfunction "P_1") (pintype "passive"))
      (node (ref "U$86") (pin "1") (pinfunction "P_1") (pintype "passive"))
      (node (ref "U$90") (pin "1") (pinfunction "P_1") (pintype "passive"))
      (node (ref "U$93") (pin "1") (pinfunction "P_1") (pintype "passive"))
      (node (ref "U$94") (pin "1") (pinfunction "P_1") (pintype "passive"))
      (node (ref "U$95") (pin "1") (pinfunction "P_1") (pintype "passive"))
      (node (ref "U$96") (pin "1") (pinfunction "P_1") (pintype "passive"))
    )
    (net (code "2") (name "A0") (class "Default")
      (node (ref "IC1") (pin "21") (pinfunction "A0_21") (pintype "input"))
      (node (ref "JP2") (pin "18") (pinfunction "18_18") (pintype "passive"))
    )
    (net (code "3") (name "A1") (class "Default")
      (node (ref "IC1") (pin "2") (pinfunction "A1_2") (pintype "input"))
      (node (ref "JP2") (pin "19") (pinfunction "19_19") (pintype "passive"))
    )
    (net (code "4") (name "A2") (class "Default")
      (node (ref "IC1") (pin "3") (pinfunction "A2_3") (pintype "input"))
      (node (ref "JP2") (pin "20") (pinfunction "20_20") (pintype "passive"))
    )
    (net (code "5") (name "GND") (class "Default")
      (node (ref "BT1") (pin "-") (pinfunction "-_-") (pintype "passive"))
      (node (ref "BT2") (pin "-") (pinfunction "-_-") (pintype "passive"))
      (node (ref "C1") (pin "2") (pinfunction "2_2") (pintype "passive"))
      (node (ref "C2") (pin "2") (pinfunction "2_2") (pintype "passive"))
      (node (ref "C3") (pin "2") (pinfunction "2_2") (pintype "passive"))
      (node (ref "C4") (pin "2") (pinfunction "2_2") (pintype "passive"))
      (node (ref "C5") (pin "2") (pinfunction "2_2") (pintype "passive"))
      (node (ref "C6") (pin "2") (pinfunction "2_2") (pintype "passive"))
      (node (ref "C7") (pin "2") (pinfunction "2_2") (pintype "passive"))
      (node (ref "IC1") (pin "12") (pinfunction "VSS_12") (pintype "power_in"))
      (node (ref "IC2") (pin "4") (pinfunction "GND_4") (pintype "power_in"))
      (node (ref "JP1") (pin "17") (pinfunction "17_17") (pintype "passive"))
      (node (ref "JP1") (pin "3") (pinfunction "3_3") (pintype "passive"))
      (node (ref "JP1") (pin "7") (pinfunction "7_7") (pintype "passive"))
      (node (ref "JP2") (pin "22") (pinfunction "22_22") (pintype "passive"))
      (node (ref "K1") (pin "14") (pinfunction "14_14") (pintype "passive"))
      (node (ref "K5") (pin "2") (pinfunction "2_2") (pintype "passive"))
      (node (ref "K6") (pin "1") (pinfunction "1_1") (pintype "passive"))
      (node (ref "R1") (pin "1") (pinfunction "1_1") (pintype "passive"))
      (node (ref "R10") (pin "1") (pinfunction "1_1") (pintype "passive"))
      (node (ref "R11") (pin "2") (pinfunction "2_2") (pintype "passive"))
      (node (ref "R13") (pin "1") (pinfunction "1_1") (pintype "passive"))
      (node (ref "R14") (pin "1") (pinfunction "1_1") (pintype "passive"))
      (node (ref "R15") (pin "1") (pinfunction "1_1") (pintype "passive"))
      (node (ref "S1") (pin "3") (pinfunction "3_3") (pintype "passive"))
      (node (ref "S1") (pin "4") (pinfunction "4_4") (pintype "passive"))
      (node (ref "S2") (pin "3") (pinfunction "3_3") (pintype "passive"))
      (node (ref "S2") (pin "4") (pinfunction "4_4") (pintype "passive"))
      (node (ref "S3") (pin "3") (pinfunction "3_3") (pintype "passive"))
      (node (ref "S3") (pin "4") (pinfunction "4_4") (pintype "passive"))
      (node (ref "T1") (pin "2") (pinfunction "S_2") (pintype "passive"))
      (node (ref "U$427") (pin "1") (pinfunction "P_1") (pintype "passive"))
      (node (ref "U$428") (pin "1") (pinfunction "P_1") (pintype "passive"))
      (node (ref "U$429") (pin "1") (pinfunction "P_1") (pintype "passive"))
      (node (ref "U$430") (pin "1") (pinfunction "P_1") (pintype "passive"))
      (node (ref "U$431") (pin "1") (pinfunction "P_1") (pintype "passive"))
    )
    (net (code "6") (name "GPA0") (class "Default")
      (node (ref "K1") (pin "1") (pinfunction "1_1") (pintype "passive"))
      (node (ref "R5") (pin "1") (pinfunction "1_1") (pintype "passive"))
      (node (ref "S1") (pin "1") (pinfunction "1_1") (pintype "passive"))
    )
    (net (code "7") (name "GPA1") (class "Default")
      (node (ref "K1") (pin "2") (pinfunction "2_2") (pintype "passive"))
      (node (ref "R6") (pin "1") (pinfunction "1_1") (pintype "passive"))
      (node (ref "S2") (pin "1") (pinfunction "1_1") (pintype "passive"))
    )
    (net (code "8") (name "GPA3") (class "Default")
      (node (ref "K1") (pin "3") (pinfunction "3_3") (pintype "passive"))
      (node (ref "R7") (pin "1") (pinfunction "1_1") (pintype "passive"))
      (node (ref "S3") (pin "1") (pinfunction "1_1") (pintype "passive"))
    )
    (net (code "9") (name "IO0.0") (class "Default")
      (node (ref "IC1") (pin "4") (pinfunction "I/O0.0_4") (pintype "bidirectional"))
      (node (ref "JP2") (pin "2") (pinfunction "2_2") (pintype "passive"))
    )
    (net (code "10") (name "IO0.1") (class "Default")
      (node (ref "IC1") (pin "5") (pinfunction "I/O0.1_5") (pintype "bidirectional"))
      (node (ref "JP2") (pin "3") (pinfunction "3_3") (pintype "passive"))
    )
    (net (code "11") (name "IO0.2") (class "Default")
      (node (ref "IC1") (pin "6") (pinfunction "I/O0.2_6") (pintype "bidirectional"))
      (node (ref "JP2") (pin "4") (pinfunction "4_4") (pintype "passive"))
    )
    (net (code "12") (name "IO0.3") (class "Default")
      (node (ref "IC1") (pin "7") (pinfunction "I/O0.3_7") (pintype "bidirectional"))
      (node (ref "JP2") (pin "5") (pinfunction "5_5") (pintype "passive"))
    )
    (net (code "13") (name "IO0.4") (class "Default")
      (node (ref "IC1") (pin "8") (pinfunction "I/O0.4_8") (pintype "bidirectional"))
      (node (ref "JP2") (pin "6") (pinfunction "6_6") (pintype "passive"))
    )
    (net (code "14") (name "IO0.5") (class "Default")
      (node (ref "IC1") (pin "9") (pinfunction "I/O0.5_9") (pintype "bidirectional"))
      (node (ref "JP2") (pin "7") (pinfunction "7_7") (pintype "passive"))
    )
    (net (code "15") (name "IO0.6") (class "Default")
      (node (ref "IC1") (pin "10") (pinfunction "I/O0.6_10") (pintype "bidirectional"))
      (node (ref "JP2") (pin "8") (pinfunction "8_8") (pintype "passive"))
    )
    (net (code "16") (name "IO0.7") (class "Default")
      (node (ref "IC1") (pin "11") (pinfunction "I/O0.7_11") (pintype "bidirectional"))
      (node (ref "JP2") (pin "9") (pinfunction "9_9") (pintype "passive"))
    )
    (net (code "17") (name "IO1.0") (class "Default")
      (node (ref "IC1") (pin "13") (pinfunction "I/O1.0_13") (pintype "bidirectional"))
      (node (ref "JP2") (pin "10") (pinfunction "10_10") (pintype "passive"))
    )
    (net (code "18") (name "IO1.1") (class "Default")
      (node (ref "IC1") (pin "14") (pinfunction "I/O1.1_14") (pintype "bidirectional"))
      (node (ref "JP2") (pin "11") (pinfunction "11_11") (pintype "passive"))
    )
    (net (code "19") (name "IO1.2") (class "Default")
      (node (ref "IC1") (pin "15") (pinfunction "I/O1.2_15") (pintype "bidirectional"))
      (node (ref "JP2") (pin "12") (pinfunction "12_12") (pintype "passive"))
    )
    (net (code "20") (name "IO1.3") (class "Default")
      (node (ref "IC1") (pin "16") (pinfunction "I/O1.3_16") (pintype "bidirectional"))
      (node (ref "JP2") (pin "13") (pinfunction "13_13") (pintype "passive"))
    )
    (net (code "21") (name "IO1.4") (class "Default")
      (node (ref "IC1") (pin "17") (pinfunction "I/O1.4_17") (pintype "bidirectional"))
      (node (ref "JP2") (pin "14") (pinfunction "14_14") (pintype "passive"))
    )
    (net (code "22") (name "IO1.5") (class "Default")
      (node (ref "IC1") (pin "18") (pinfunction "I/O1.5_18") (pintype "bidirectional"))
      (node (ref "JP2") (pin "15") (pinfunction "15_15") (pintype "passive"))
    )
    (net (code "23") (name "IO1.6") (class "Default")
      (node (ref "IC1") (pin "19") (pinfunction "I/O1.6_19") (pintype "bidirectional"))
      (node (ref "JP2") (pin "16") (pinfunction "16_16") (pintype "passive"))
    )
    (net (code "24") (name "IO1.7") (class "Default")
      (node (ref "IC1") (pin "20") (pinfunction "I/O1.7_20") (pintype "bidirectional"))
      (node (ref "JP2") (pin "17") (pinfunction "17_17") (pintype "passive"))
    )
    (net (code "25") (name "IO11") (class "Default")
      (node (ref "JP1") (pin "18") (pinfunction "18_18") (pintype "passive"))
      (node (ref "K1") (pin "12") (pinfunction "12_12") (pintype "passive"))
      (node (ref "R14") (pin "2") (pinfunction "2_2") (pintype "passive"))
    )
    (net (code "26") (name "IO14") (class "Default")
      (node (ref "JP1") (pin "19") (pinfunction "19_19") (pintype "passive"))
      (node (ref "K1") (pin "11") (pinfunction "11_11") (pintype "passive"))
      (node (ref "R13") (pin "2") (pinfunction "2_2") (pintype "passive"))
    )
    (net (code "27") (name "MISO") (class "Default")
      (node (ref "K1") (pin "8") (pinfunction "8_8") (pintype "passive"))
    )
    (net (code "28") (name "MOSI") (class "Default")
      (node (ref "JP1") (pin "8") (pinfunction "8_8") (pintype "passive"))
      (node (ref "K1") (pin "7") (pinfunction "7_7") (pintype "passive"))
      (node (ref "R11") (pin "1") (pinfunction "1_1") (pintype "passive"))
    )
    (net (code "29") (name "Net-(C8-Pad1)") (class "Default")
      (node (ref "C8") (pin "1") (pinfunction "1_1") (pintype "passive"))
      (node (ref "JP1") (pin "1") (pinfunction "1_1") (pintype "passive"))
    )
    (net (code "30") (name "Net-(C8-Pad2)") (class "Default")
      (node (ref "C8") (pin "2") (pinfunction "2_2") (pintype "passive"))
      (node (ref "JP1") (pin "2") (pinfunction "2_2") (pintype "passive"))
    )
    (net (code "31") (name "Net-(C9-Pad1)") (class "Default")
      (node (ref "C9") (pin "1") (pinfunction "1_1") (pintype "passive"))
      (node (ref "JP1") (pin "4") (pinfunction "4_4") (pintype "passive"))
    )
    (net (code "32") (name "Net-(IC2-MFP)") (class "Default")
      (node (ref "IC2") (pin "7") (pinfunction "MFP_7") (pintype "bidirectional"))
      (node (ref "R2") (pin "1") (pinfunction "1_1") (pintype "passive"))
    )
    (net (code "33") (name "Net-(IC2-VBAT)") (class "Default")
      (node (ref "BT1") (pin "+") (pinfunction "+_+") (pintype "passive"))
      (node (ref "BT2") (pin "+") (pinfunction "+_+") (pintype "passive"))
      (node (ref "IC2") (pin "3") (pinfunction "VBAT_3") (pintype "power_in"))
    )
    (net (code "34") (name "Net-(IC2-X1)") (class "Default")
      (node (ref "C4") (pin "1") (pinfunction "1_1") (pintype "passive"))
      (node (ref "IC2") (pin "1") (pinfunction "X1_1") (pintype "input"))
      (node (ref "X2") (pin "2") (pinfunction "2_2") (pintype "passive"))
    )
    (net (code "35") (name "Net-(IC2-X2)") (class "Default")
      (node (ref "C3") (pin "1") (pinfunction "1_1") (pintype "passive"))
      (node (ref "IC2") (pin "2") (pinfunction "X2_2") (pintype "output"))
      (node (ref "X2") (pin "1") (pinfunction "1_1") (pintype "passive"))
    )
    (net (code "36") (name "Net-(JP1-Pad10)") (class "Default")
      (node (ref "JP1") (pin "10") (pinfunction "10_10") (pintype "passive"))
      (node (ref "JP1") (pin "11") (pinfunction "11_11") (pintype "passive"))
      (node (ref "JP1") (pin "12") (pinfunction "12_12") (pintype "passive"))
      (node (ref "JP1") (pin "13") (pinfunction "13_13") (pintype "passive"))
      (node (ref "JP1") (pin "14") (pinfunction "14_14") (pintype "passive"))
      (node (ref "JP1") (pin "15") (pinfunction "15_15") (pintype "passive"))
      (node (ref "JP1") (pin "16") (pinfunction "16_16") (pintype "passive"))
      (node (ref "JP1") (pin "20") (pinfunction "20_20") (pintype "passive"))
      (node (ref "R12") (pin "2") (pinfunction "2_2") (pintype "passive"))
    )
    (net (code "37") (name "Net-(K5-Pad1)") (class "Default")
      (node (ref "K5") (pin "1") (pinfunction "1_1") (pintype "passive"))
      (node (ref "R8") (pin "1") (pinfunction "1_1") (pintype "passive"))
    )
    (net (code "38") (name "Net-(K6-Pad2)") (class "Default")
      (node (ref "K6") (pin "2") (pinfunction "2_2") (pintype "passive"))
      (node (ref "R9") (pin "2") (pinfunction "2_2") (pintype "passive"))
    )
    (net (code "39") (name "Net-(T1-D)") (class "Default")
      (node (ref "BZ1") (pin "-") (pinfunction "-_-") (pintype "passive"))
      (node (ref "T1") (pin "3") (pinfunction "D_3") (pintype "passive"))
    )
    (net (code "40") (name "PWM") (class "Default")
      (node (ref "C7") (pin "1") (pinfunction "1_1") (pintype "passive"))
      (node (ref "K1") (pin "4") (pinfunction "4_4") (pintype "passive"))
      (node (ref "R1") (pin "2") (pinfunction "2_2") (pintype "passive"))
      (node (ref "T1") (pin "1") (pinfunction "G_1") (pintype "passive"))
    )
    (net (code "41") (name "SCK") (class "Default")
      (node (ref "JP1") (pin "9") (pinfunction "9_9") (pintype "passive"))
      (node (ref "K1") (pin "10") (pinfunction "10_10") (pintype "passive"))
      (node (ref "R10") (pin "2") (pinfunction "2_2") (pintype "passive"))
    )
    (net (code "42") (name "SCL") (class "Default")
      (node (ref "IC1") (pin "22") (pinfunction "SCL_22") (pintype "input"))
      (node (ref "IC2") (pin "6") (pinfunction "SCL_6") (pintype "bidirectional"))
      (node (ref "K1") (pin "5") (pinfunction "5_5") (pintype "passive"))
      (node (ref "R3") (pin "1") (pinfunction "1_1") (pintype "passive"))
    )
    (net (code "43") (name "SDA") (class "Default")
      (node (ref "IC1") (pin "23") (pinfunction "SDA_23") (pintype "bidirectional"))
      (node (ref "IC2") (pin "5") (pinfunction "SDA_5") (pintype "bidirectional"))
      (node (ref "K1") (pin "6") (pinfunction "6_6") (pintype "passive"))
      (node (ref "R4") (pin "1") (pinfunction "1_1") (pintype "passive"))
    )
    (net (code "44") (name "SYSCLK") (class "Default")
      (node (ref "K1") (pin "9") (pinfunction "9_9") (pintype "passive"))
    )
    (net (code "45") (name "unconnected-(S1-Pad2)") (class "Default")
      (node (ref "S1") (pin "2") (pinfunction "2_2") (pintype "passive"))
    )
    (net (code "46") (name "unconnected-(S2-Pad2)") (class "Default")
      (node (ref "S2") (pin "2") (pinfunction "2_2") (pintype "passive"))
    )
    (net (code "47") (name "unconnected-(S3-Pad2)") (class "Default")
      (node (ref "S3") (pin "2") (pinfunction "2_2") (pintype "passive"))
    )
    (net (code "48") (name "~{INT}") (class "Default")
      (node (ref "IC1") (pin "1") (pinfunction "~{INT}_1") (pintype "output"))
      (node (ref "JP2") (pin "21") (pinfunction "21_21") (pintype "passive"))
      (node (ref "R15") (pin "2") (pinfunction "2_2") (pintype "passive"))
    )
  )
)
